# RTDAnalog.net
KiCad netlist of a schematic drawn in Altium Designer
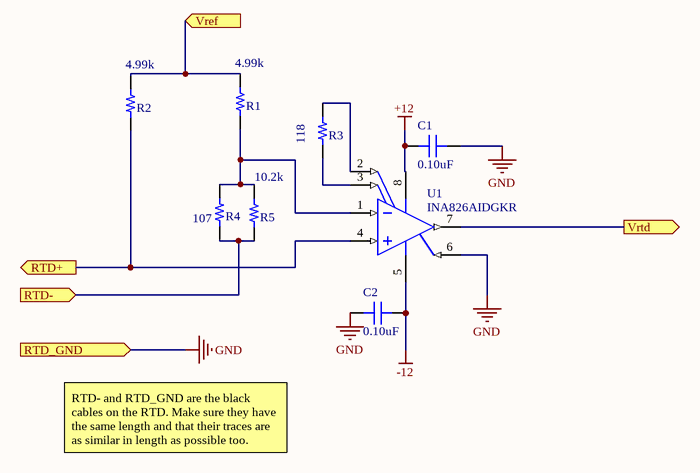
[diagram p0: RTDAnalog.SchDoc]

(export (version "E")
  (design (tool "Eeschema 10.0.6"))
  (components
    (comp (ref "C1")
      (value "0.10uF")
      (footprint "CAP 0402/1005")
      (description "CAP CER 0.1UF 16V X7R 0402")
      (fields
        (field (name "PART NUMBER") "GRM155R71C104JA88D")
        (field (name "MANUFACTURER") "Murata Electronics North America")
      )
      (libsource (lib "Celestial Library Database") (part "Capacitor"))
    )
    (comp (ref "C2")
      (value "0.10uF")
      (footprint "CAP 0402/1005")
      (description "CAP CER 0.1UF 16V X7R 0402")
      (fields
        (field (name "PART NUMBER") "GRM155R71C104JA88D")
        (field (name "MANUFACTURER") "Murata Electronics North America")
      )
      (libsource (lib "Celestial Library Database") (part "Capacitor"))
    )
    (comp (ref "R1")
      (value "4.99k")
      (footprint "RES 0805/2012")
      (description "RES SMD 4.99K OHM 0.1% 1/8W 0805")
      (fields
        (field (name "PART NUMBER") "ERA-6AEB4991V")
        (field (name "MANUFACTURER") "Panasonic Electronic Components")
      )
      (libsource (lib "Celestial Library Database") (part "Resistor"))
    )
    (comp (ref "R2")
      (value "4.99k")
      (footprint "RES 0805/2012")
      (description "RES SMD 4.99K OHM 0.1% 1/8W 0805")
      (fields
        (field (name "PART NUMBER") "ERA-6AEB4991V")
        (field (name "MANUFACTURER") "Panasonic Electronic Components")
      )
      (libsource (lib "Celestial Library Database") (part "Resistor"))
    )
    (comp (ref "R3")
      (value "118")
      (footprint "RES 0805/2012")
      (description "RES SMD 118 OHM 0.1% 1/8W 0805")
      (fields
        (field (name "PART NUMBER") "ERA-6AEB1180V")
        (field (name "MANUFACTURER") "Panasonic Electronic Components")
      )
      (libsource (lib "Celestial Library Database") (part "Resistor"))
    )
    (comp (ref "R4")
      (value "107")
      (footprint "RES 0805/2012")
      (description "RES SMD 107 OHM 0.1% 1/8W 0805")
      (fields
        (field (name "PART NUMBER") "ERA-6AEB1070V")
        (field (name "MANUFACTURER") "Panasonic Electronic Components")
      )
      (libsource (lib "Celestial Library Database") (part "Resistor"))
    )
    (comp (ref "R5")
      (value "10.2k")
      (footprint "RES 0805/2012")
      (description "RES SMD 10.2K OHM 0.1% 1/8W 0805")
      (fields
        (field (name "PART NUMBER") "ERA-6AEB1022V")
        (field (name "MANUFACTURER") "Panasonic Electronic Components")
      )
      (libsource (lib "Celestial Library Database") (part "Resistor"))
    )
    (comp (ref "U1")
      (value "INA826AIDGKR")
      (footprint "DGK0008A_N")
      (fields (field (name "MANUFACTURER") "Texas Instruments"))
      (libsource (lib "Altium Content Vault") (part "TI-INA826X8"))
    )
  )
  (nets
    (net (code "1") (name "+12") (class "Default")
      (node (ref "C1") (pin "1") (pinfunction "1_1") (pintype "passive"))
      (node (ref "U1") (pin "8") (pinfunction "VS+_8") (pintype "power_in"))
    )
    (net (code "2") (name "-12") (class "Default")
      (node (ref "C2") (pin "2") (pinfunction "2_2") (pintype "passive"))
      (node (ref "U1") (pin "5") (pinfunction "VS-_5") (pintype "power_in"))
    )
    (net (code "3") (name "/RTD+") (class "Default")
      (node (ref "R2") (pin "1") (pinfunction "1_1") (pintype "passive"))
      (node (ref "U1") (pin "4") (pinfunction "IN+_4") (pintype "input"))
    )
    (net (code "4") (name "/RTD-") (class "Default")
      (node (ref "R4") (pin "1") (pinfunction "1_1") (pintype "passive"))
      (node (ref "R5") (pin "1") (pinfunction "1_1") (pintype "passive"))
    )
    (net (code "5") (name "/Vref") (class "Default")
      (node (ref "R1") (pin "2") (pinfunction "2_2") (pintype "passive"))
      (node (ref "R2") (pin "2") (pinfunction "2_2") (pintype "passive"))
    )
    (net (code "6") (name "/Vrtd") (class "Default")
      (node (ref "U1") (pin "7") (pinfunction "VOUT_7") (pintype "output"))
    )
    (net (code "7") (name "GND") (class "Default")
      (node (ref "C1") (pin "2") (pinfunction "2_2") (pintype "passive"))
      (node (ref "C2") (pin "1") (pinfunction "1_1") (pintype "passive"))
      (node (ref "U1") (pin "6") (pinfunction "REF_6") (pintype "input"))
    )
    (net (code "8") (name "Net-(R3-Pad1)") (class "Default")
      (node (ref "R3") (pin "1") (pinfunction "1_1") (pintype "passive"))
      (node (ref "U1") (pin "3") (pinfunction "RG_3") (pintype "input"))
    )
    (net (code "9") (name "Net-(R3-Pad2)") (class "Default")
      (node (ref "R3") (pin "2") (pinfunction "2_2") (pintype "passive"))
      (node (ref "U1") (pin "2") (pinfunction "RG_2") (pintype "input"))
    )
    (net (code "10") (name "Net-(U1-IN-)") (class "Default")
      (node (ref "R1") (pin "1") (pinfunction "1_1") (pintype "passive"))
      (node (ref "R4") (pin "2") (pinfunction "2_2") (pintype "passive"))
      (node (ref "R5") (pin "2") (pinfunction "2_2") (pintype "passive"))
      (node (ref "U1") (pin "1") (pinfunction "IN-_1") (pintype "input"))
    )
  )
)
